# LCD_shield_C144MVGD_v1.net
KiCad netlist of a schematic drawn in EAGLE
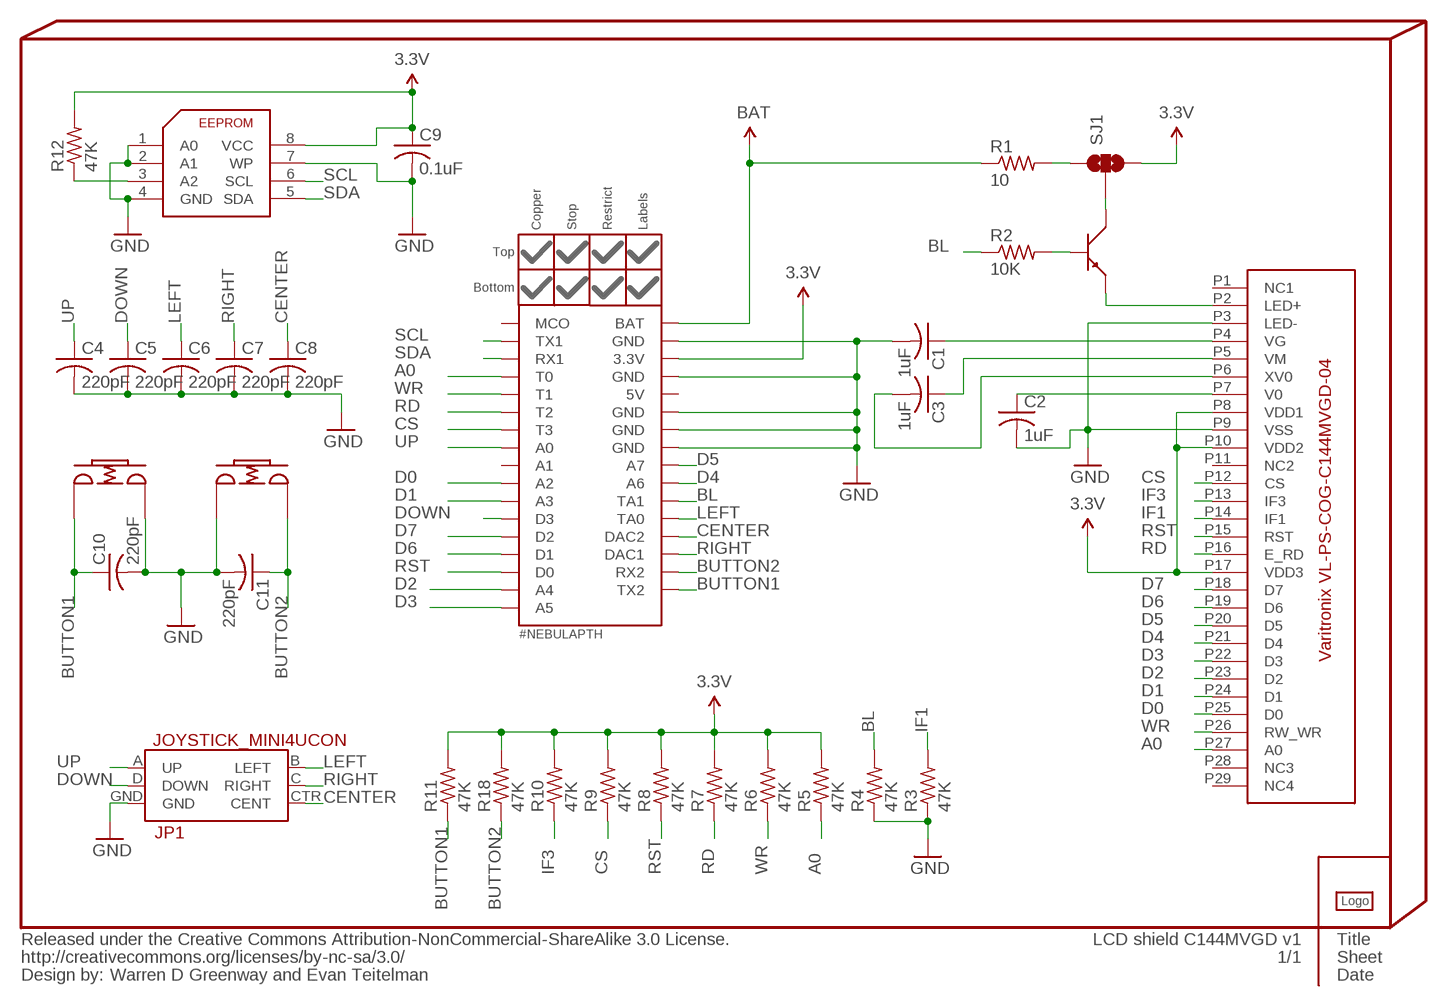
[diagram p0: schematic, sheet 1]

(export (version "E")
  (design (tool "Eeschema 10.0.6"))
  (components
    (comp (ref "C1")
      (value "1uF")
      (footprint "eagle-import:C0402")
      (libsource (lib "eagle-import") (part "C-USC0402"))
    )
    (comp (ref "C2")
      (value "1uF")
      (footprint "eagle-import:C0402")
      (libsource (lib "eagle-import") (part "C-USC0402"))
    )
    (comp (ref "C3")
      (value "1uF")
      (footprint "eagle-import:C0402")
      (libsource (lib "eagle-import") (part "C-USC0402"))
    )
    (comp (ref "C4")
      (value "220pF")
      (footprint "eagle-import:C0402")
      (libsource (lib "eagle-import") (part "C-USC0402"))
    )
    (comp (ref "C5")
      (value "220pF")
      (footprint "eagle-import:C0402")
      (libsource (lib "eagle-import") (part "C-USC0402"))
    )
    (comp (ref "C6")
      (value "220pF")
      (footprint "eagle-import:C0402")
      (libsource (lib "eagle-import") (part "C-USC0402"))
    )
    (comp (ref "C7")
      (value "220pF")
      (footprint "eagle-import:C0402")
      (libsource (lib "eagle-import") (part "C-USC0402"))
    )
    (comp (ref "C8")
      (value "220pF")
      (footprint "eagle-import:C0402")
      (libsource (lib "eagle-import") (part "C-USC0402"))
    )
    (comp (ref "C9")
      (value "0.1uF")
      (footprint "eagle-import:C0402")
      (libsource (lib "eagle-import") (part "C-USC0402"))
    )
    (comp (ref "C10")
      (value "220pF")
      (footprint "eagle-import:C0402")
      (libsource (lib "eagle-import") (part "C-USC0402"))
    )
    (comp (ref "C11")
      (value "220pF")
      (footprint "eagle-import:C0402")
      (libsource (lib "eagle-import") (part "C-USC0402"))
    )
    (comp (ref "INFO3")
      (value "Warren D Greenway and Evan Teitelman")
      (footprint "eagle-import:%CC-NC-SA")
      (libsource (lib "eagle-import") (part "%CC-NC-SA"))
    )
    (comp (ref "JP1")
      (value "JOYSTICK_MINI4UCON")
      (footprint "eagle-import:JOYSTICK_MINI")
      (libsource (lib "eagle-import") (part "JOYSTICK_MINI4UCON"))
    )
    (comp (ref "LOGO1")
      (value "#PYGMYLOGOLARGE")
      (footprint "eagle-import:#PYGMYLOGO")
      (libsource (lib "eagle-import") (part "#PYGMYLOGOLARGE"))
    )
    (comp (ref "NEBULA1")
      (value "#NEBULAPTH")
      (footprint "eagle-import:#NEBULA-PTH")
      (libsource (lib "eagle-import") (part "#NEBULAPTH"))
    )
    (comp (ref "R1")
      (value "10")
      (footprint "eagle-import:R0805")
      (libsource (lib "eagle-import") (part "R-US_R0805"))
    )
    (comp (ref "R2")
      (value "10K")
      (footprint "eagle-import:R0402")
      (libsource (lib "eagle-import") (part "R-US_R0402"))
    )
    (comp (ref "R3")
      (value "47K")
      (footprint "eagle-import:R0402")
      (libsource (lib "eagle-import") (part "R-US_R0402"))
    )
    (comp (ref "R4")
      (value "47K")
      (footprint "eagle-import:R0402")
      (libsource (lib "eagle-import") (part "R-US_R0402"))
    )
    (comp (ref "R5")
      (value "47K")
      (footprint "eagle-import:R0402")
      (libsource (lib "eagle-import") (part "R-US_R0402"))
    )
    (comp (ref "R6")
      (value "47K")
      (footprint "eagle-import:R0402")
      (libsource (lib "eagle-import") (part "R-US_R0402"))
    )
    (comp (ref "R7")
      (value "47K")
      (footprint "eagle-import:R0402")
      (libsource (lib "eagle-import") (part "R-US_R0402"))
    )
    (comp (ref "R8")
      (value "47K")
      (footprint "eagle-import:R0402")
      (libsource (lib "eagle-import") (part "R-US_R0402"))
    )
    (comp (ref "R9")
      (value "47K")
      (footprint "eagle-import:R0402")
      (libsource (lib "eagle-import") (part "R-US_R0402"))
    )
    (comp (ref "R10")
      (value "47K")
      (footprint "eagle-import:R0402")
      (libsource (lib "eagle-import") (part "R-US_R0402"))
    )
    (comp (ref "R11")
      (value "47K")
      (footprint "eagle-import:R0402")
      (libsource (lib "eagle-import") (part "R-US_R0402"))
    )
    (comp (ref "R12")
      (value "47K")
      (footprint "eagle-import:R0402")
      (libsource (lib "eagle-import") (part "R-US_R0402"))
    )
    (comp (ref "R18")
      (value "47K")
      (footprint "eagle-import:R0402")
      (libsource (lib "eagle-import") (part "R-US_R0402"))
    )
    (comp (ref "SJ1")
      (value "SOLDERJUMPER_2WAYPASTE1&2")
      (footprint "eagle-import:SJ_3_PASTE1&2")
      (libsource (lib "eagle-import") (part "SOLDERJUMPER_2WAYPASTE1&2"))
    )
    (comp (ref "U1")
      (value "VARITRONIX_VL-PS-COG-C144MVGD-04FOLDED")
      (footprint "eagle-import:VARITRONIX_C144MVGD_FOLDED")
      (libsource (lib "eagle-import") (part "VARITRONIX_VL-PS-COG-C144MVGD-04FOLDED"))
    )
    (comp (ref "U2")
      (value "BIPOLAR-PMBT6428")
      (footprint "eagle-import:DUBLIB_SOT23")
      (libsource (lib "eagle-import") (part "BIPOLAR-PMBT6428"))
    )
    (comp (ref "U3")
      (value "EEPROM-ATMEL-AT24HC02B")
      (footprint "eagle-import:TSSOP8")
      (libsource (lib "eagle-import") (part "EEPROM-ATMEL-AT24HC02B"))
    )
    (comp (ref "U4")
      (value "SWITCH-ALPS-SKRG")
      (footprint "eagle-import:SWITCH-2P-5MM")
      (libsource (lib "eagle-import") (part "SWITCH-ALPS-SKRG"))
    )
    (comp (ref "U5")
      (value "SWITCH-ALPS-SKRG")
      (footprint "eagle-import:SWITCH-2P-5MM")
      (libsource (lib "eagle-import") (part "SWITCH-ALPS-SKRG"))
    )
  )
  (nets
    (net (code "1") (name "/A0") (class "Default")
      (node (ref "NEBULA1") (pin "T0") (pinfunction "T0_T0") (pintype "bidirectional"))
      (node (ref "R5") (pin "1") (pinfunction "1_1") (pintype "passive"))
      (node (ref "U1") (pin "P27") (pinfunction "A0_P27") (pintype "bidirectional"))
    )
    (net (code "2") (name "/BL") (class "Default")
      (node (ref "NEBULA1") (pin "TA1") (pinfunction "TA1_TA1") (pintype "bidirectional"))
      (node (ref "R2") (pin "1") (pinfunction "1_1") (pintype "passive"))
      (node (ref "R4") (pin "2") (pinfunction "2_2") (pintype "passive"))
    )
    (net (code "3") (name "/BUTTON1") (class "Default")
      (node (ref "C10") (pin "1") (pinfunction "1_1") (pintype "passive"))
      (node (ref "NEBULA1") (pin "COM2_TX") (pinfunction "TX2_COM2_TX") (pintype "bidirectional"))
      (node (ref "R11") (pin "1") (pinfunction "1_1") (pintype "passive"))
      (node (ref "U4") (pin "P1") (pinfunction "P1_P1") (pintype "bidirectional"))
    )
    (net (code "4") (name "/BUTTON2") (class "Default")
      (node (ref "C11") (pin "1") (pinfunction "1_1") (pintype "passive"))
      (node (ref "NEBULA1") (pin "COM2_RX") (pinfunction "RX2_COM2_RX") (pintype "bidirectional"))
      (node (ref "R18") (pin "1") (pinfunction "1_1") (pintype "passive"))
      (node (ref "U5") (pin "P2") (pinfunction "P2_P2") (pintype "bidirectional"))
    )
    (net (code "5") (name "/CENTER") (class "Default")
      (node (ref "C8") (pin "1") (pinfunction "1_1") (pintype "passive"))
      (node (ref "JP1") (pin "CTR") (pinfunction "CENT_CTR") (pintype "bidirectional"))
      (node (ref "NEBULA1") (pin "DAC2") (pinfunction "DAC2_DAC2") (pintype "bidirectional"))
    )
    (net (code "6") (name "/CS") (class "Default")
      (node (ref "NEBULA1") (pin "T3") (pinfunction "T3_T3") (pintype "bidirectional"))
      (node (ref "R9") (pin "1") (pinfunction "1_1") (pintype "passive"))
      (node (ref "U1") (pin "P12") (pinfunction "CS_P12") (pintype "bidirectional"))
    )
    (net (code "7") (name "/D0") (class "Default")
      (node (ref "NEBULA1") (pin "A2") (pinfunction "A2_A2") (pintype "bidirectional"))
      (node (ref "U1") (pin "P25") (pinfunction "D0_P25") (pintype "bidirectional"))
    )
    (net (code "8") (name "/D1") (class "Default")
      (node (ref "NEBULA1") (pin "A3") (pinfunction "A3_A3") (pintype "bidirectional"))
      (node (ref "U1") (pin "P24") (pinfunction "D1_P24") (pintype "bidirectional"))
    )
    (net (code "9") (name "/D2") (class "Default")
      (node (ref "NEBULA1") (pin "A4") (pinfunction "A4_A4") (pintype "bidirectional"))
      (node (ref "U1") (pin "P23") (pinfunction "D2_P23") (pintype "bidirectional"))
    )
    (net (code "10") (name "/D3") (class "Default")
      (node (ref "NEBULA1") (pin "A5") (pinfunction "A5_A5") (pintype "bidirectional"))
      (node (ref "U1") (pin "P22") (pinfunction "D3_P22") (pintype "bidirectional"))
    )
    (net (code "11") (name "/D4") (class "Default")
      (node (ref "NEBULA1") (pin "A6") (pinfunction "A6_A6") (pintype "bidirectional"))
      (node (ref "U1") (pin "P21") (pinfunction "D4_P21") (pintype "bidirectional"))
    )
    (net (code "12") (name "/D5") (class "Default")
      (node (ref "NEBULA1") (pin "A7") (pinfunction "A7_A7") (pintype "bidirectional"))
      (node (ref "U1") (pin "P20") (pinfunction "D5_P20") (pintype "bidirectional"))
    )
    (net (code "13") (name "/D6") (class "Default")
      (node (ref "NEBULA1") (pin "D1") (pinfunction "D1_D1") (pintype "bidirectional"))
      (node (ref "U1") (pin "P19") (pinfunction "D6_P19") (pintype "bidirectional"))
    )
    (net (code "14") (name "/D7") (class "Default")
      (node (ref "NEBULA1") (pin "D2") (pinfunction "D2_D2") (pintype "bidirectional"))
      (node (ref "U1") (pin "P18") (pinfunction "D7_P18") (pintype "bidirectional"))
    )
    (net (code "15") (name "/DOWN") (class "Default")
      (node (ref "C5") (pin "1") (pinfunction "1_1") (pintype "passive"))
      (node (ref "JP1") (pin "D") (pinfunction "DOWN_D") (pintype "bidirectional"))
      (node (ref "NEBULA1") (pin "D3") (pinfunction "D3_D3") (pintype "bidirectional"))
    )
    (net (code "16") (name "/IF1") (class "Default")
      (node (ref "R3") (pin "2") (pinfunction "2_2") (pintype "passive"))
      (node (ref "U1") (pin "P14") (pinfunction "IF1_P14") (pintype "bidirectional"))
    )
    (net (code "17") (name "/IF3") (class "Default")
      (node (ref "R10") (pin "1") (pinfunction "1_1") (pintype "passive"))
      (node (ref "U1") (pin "P13") (pinfunction "IF3_P13") (pintype "bidirectional"))
    )
    (net (code "18") (name "/LEFT") (class "Default")
      (node (ref "C6") (pin "1") (pinfunction "1_1") (pintype "passive"))
      (node (ref "JP1") (pin "B") (pinfunction "LEFT_B") (pintype "bidirectional"))
      (node (ref "NEBULA1") (pin "TA0") (pinfunction "TA0_TA0") (pintype "bidirectional"))
    )
    (net (code "19") (name "/RD") (class "Default")
      (node (ref "NEBULA1") (pin "T2") (pinfunction "T2_T2") (pintype "bidirectional"))
      (node (ref "R7") (pin "1") (pinfunction "1_1") (pintype "passive"))
      (node (ref "U1") (pin "P16") (pinfunction "E_RD_P16") (pintype "bidirectional"))
    )
    (net (code "20") (name "/RIGHT") (class "Default")
      (node (ref "C7") (pin "1") (pinfunction "1_1") (pintype "passive"))
      (node (ref "JP1") (pin "C") (pinfunction "RIGHT_C") (pintype "bidirectional"))
      (node (ref "NEBULA1") (pin "DAC1") (pinfunction "DAC1_DAC1") (pintype "bidirectional"))
    )
    (net (code "21") (name "/RST") (class "Default")
      (node (ref "NEBULA1") (pin "D0") (pinfunction "D0_D0") (pintype "bidirectional"))
      (node (ref "R8") (pin "1") (pinfunction "1_1") (pintype "passive"))
      (node (ref "U1") (pin "P15") (pinfunction "RST_P15") (pintype "bidirectional"))
    )
    (net (code "22") (name "/SCL") (class "Default")
      (node (ref "NEBULA1") (pin "COM1_TX") (pinfunction "TX1_COM1_TX") (pintype "bidirectional"))
      (node (ref "U3") (pin "6") (pinfunction "SCL_6") (pintype "bidirectional"))
    )
    (net (code "23") (name "/SDA") (class "Default")
      (node (ref "NEBULA1") (pin "COM1_RX") (pinfunction "RX1_COM1_RX") (pintype "bidirectional"))
      (node (ref "U3") (pin "5") (pinfunction "SDA_5") (pintype "bidirectional"))
    )
    (net (code "24") (name "/UP") (class "Default")
      (node (ref "C4") (pin "1") (pinfunction "1_1") (pintype "passive"))
      (node (ref "JP1") (pin "A") (pinfunction "UP_A") (pintype "bidirectional"))
      (node (ref "NEBULA1") (pin "A0") (pinfunction "A0_A0") (pintype "bidirectional"))
    )
    (net (code "25") (name "/WR") (class "Default")
      (node (ref "NEBULA1") (pin "T1") (pinfunction "T1_T1") (pintype "bidirectional"))
      (node (ref "R6") (pin "1") (pinfunction "1_1") (pintype "passive"))
      (node (ref "U1") (pin "P26") (pinfunction "RW_WR_P26") (pintype "bidirectional"))
    )
    (net (code "26") (name "@3.3V") (class "Default")
      (node (ref "C9") (pin "1") (pinfunction "1_1") (pintype "passive"))
      (node (ref "NEBULA1") (pin "3.3V") (pinfunction "3.3V_3.3V") (pintype "bidirectional"))
      (node (ref "R10") (pin "2") (pinfunction "2_2") (pintype "passive"))
      (node (ref "R11") (pin "2") (pinfunction "2_2") (pintype "passive"))
      (node (ref "R12") (pin "2") (pinfunction "2_2") (pintype "passive"))
      (node (ref "R18") (pin "2") (pinfunction "2_2") (pintype "passive"))
      (node (ref "R5") (pin "2") (pinfunction "2_2") (pintype "passive"))
      (node (ref "R6") (pin "2") (pinfunction "2_2") (pintype "passive"))
      (node (ref "R7") (pin "2") (pinfunction "2_2") (pintype "passive"))
      (node (ref "R8") (pin "2") (pinfunction "2_2") (pintype "passive"))
      (node (ref "R9") (pin "2") (pinfunction "2_2") (pintype "passive"))
      (node (ref "SJ1") (pin "3") (pinfunction "3_3") (pintype "passive"))
      (node (ref "U1") (pin "P10") (pinfunction "VDD2_P10") (pintype "bidirectional"))
      (node (ref "U1") (pin "P17") (pinfunction "VDD3_P17") (pintype "bidirectional"))
      (node (ref "U1") (pin "P8") (pinfunction "VDD1_P8") (pintype "bidirectional"))
      (node (ref "U3") (pin "8") (pinfunction "VCC_8") (pintype "bidirectional"))
    )
    (net (code "27") (name "@BAT") (class "Default")
      (node (ref "NEBULA1") (pin "BAT") (pinfunction "BAT_BAT") (pintype "bidirectional"))
      (node (ref "R1") (pin "1") (pinfunction "1_1") (pintype "passive"))
    )
    (net (code "28") (name "@GND") (class "Default")
      (node (ref "C1") (pin "2") (pinfunction "2_2") (pintype "passive"))
      (node (ref "C10") (pin "2") (pinfunction "2_2") (pintype "passive"))
      (node (ref "C11") (pin "2") (pinfunction "2_2") (pintype "passive"))
      (node (ref "C2") (pin "2") (pinfunction "2_2") (pintype "passive"))
      (node (ref "C4") (pin "2") (pinfunction "2_2") (pintype "passive"))
      (node (ref "C5") (pin "2") (pinfunction "2_2") (pintype "passive"))
      (node (ref "C6") (pin "2") (pinfunction "2_2") (pintype "passive"))
      (node (ref "C7") (pin "2") (pinfunction "2_2") (pintype "passive"))
      (node (ref "C8") (pin "2") (pinfunction "2_2") (pintype "passive"))
      (node (ref "C9") (pin "2") (pinfunction "2_2") (pintype "passive"))
      (node (ref "JP1") (pin "GND") (pinfunction "GND_GND") (pintype "bidirectional"))
      (node (ref "NEBULA1") (pin "GND1") (pinfunction "GND_GND1") (pintype "bidirectional"))
      (node (ref "NEBULA1") (pin "GND2") (pinfunction "GND_GND2") (pintype "bidirectional"))
      (node (ref "NEBULA1") (pin "GND3") (pinfunction "GND_GND3") (pintype "bidirectional"))
      (node (ref "NEBULA1") (pin "GND4") (pinfunction "GND_GND4") (pintype "bidirectional"))
      (node (ref "NEBULA1") (pin "GND5") (pinfunction "GND_GND5") (pintype "bidirectional"))
      (node (ref "R3") (pin "1") (pinfunction "1_1") (pintype "passive"))
      (node (ref "R4") (pin "1") (pinfunction "1_1") (pintype "passive"))
      (node (ref "U1") (pin "P3") (pinfunction "LED-_P3") (pintype "bidirectional"))
      (node (ref "U1") (pin "P9") (pinfunction "VSS_P9") (pintype "bidirectional"))
      (node (ref "U3") (pin "1") (pinfunction "A0_1") (pintype "bidirectional"))
      (node (ref "U3") (pin "2") (pinfunction "A1_2") (pintype "bidirectional"))
      (node (ref "U3") (pin "4") (pinfunction "GND_4") (pintype "bidirectional"))
      (node (ref "U3") (pin "7") (pinfunction "WP_7") (pintype "bidirectional"))
      (node (ref "U4") (pin "P2") (pinfunction "P2_P2") (pintype "bidirectional"))
      (node (ref "U5") (pin "P1") (pinfunction "P1_P1") (pintype "bidirectional"))
    )
    (net (code "29") (name "Net-(R1-Pad2)") (class "Default")
      (node (ref "R1") (pin "2") (pinfunction "2_2") (pintype "passive"))
      (node (ref "SJ1") (pin "1") (pinfunction "1_1") (pintype "passive"))
    )
    (net (code "30") (name "Net-(R2-Pad2)") (class "Default")
      (node (ref "R2") (pin "2") (pinfunction "2_2") (pintype "passive"))
      (node (ref "U2") (pin "1") (pinfunction "1_1") (pintype "bidirectional"))
    )
    (net (code "31") (name "Net-(SJ1-Pad2)") (class "Default")
      (node (ref "SJ1") (pin "2") (pinfunction "2_2") (pintype "passive"))
      (node (ref "U2") (pin "3") (pinfunction "3_3") (pintype "bidirectional"))
    )
    (net (code "32") (name "Net-(U1-LED+)") (class "Default")
      (node (ref "U1") (pin "P2") (pinfunction "LED+_P2") (pintype "bidirectional"))
      (node (ref "U2") (pin "2") (pinfunction "2_2") (pintype "bidirectional"))
    )
    (net (code "33") (name "Net-(U1-V0)") (class "Default")
      (node (ref "C2") (pin "1") (pinfunction "1_1") (pintype "passive"))
      (node (ref "U1") (pin "P7") (pinfunction "V0_P7") (pintype "bidirectional"))
    )
    (net (code "34") (name "Net-(U1-VG)") (class "Default")
      (node (ref "C1") (pin "1") (pinfunction "1_1") (pintype "passive"))
      (node (ref "U1") (pin "P4") (pinfunction "VG_P4") (pintype "bidirectional"))
    )
    (net (code "35") (name "Net-(U1-VM)") (class "Default")
      (node (ref "C3") (pin "1") (pinfunction "1_1") (pintype "passive"))
      (node (ref "U1") (pin "P5") (pinfunction "VM_P5") (pintype "bidirectional"))
    )
    (net (code "36") (name "Net-(U1-XV0)") (class "Default")
      (node (ref "C3") (pin "2") (pinfunction "2_2") (pintype "passive"))
      (node (ref "U1") (pin "P6") (pinfunction "XV0_P6") (pintype "bidirectional"))
    )
    (net (code "37") (name "Net-(U3-A2)") (class "Default")
      (node (ref "R12") (pin "1") (pinfunction "1_1") (pintype "passive"))
      (node (ref "U3") (pin "3") (pinfunction "A2_3") (pintype "bidirectional"))
    )
    (net (code "38") (name "unconnected-(NEBULA1-Pad5V)") (class "Default")
      (node (ref "NEBULA1") (pin "5V") (pinfunction "5V_5V") (pintype "bidirectional"))
    )
    (net (code "39") (name "unconnected-(NEBULA1-PadA1)") (class "Default")
      (node (ref "NEBULA1") (pin "A1") (pinfunction "A1_A1") (pintype "bidirectional"))
    )
    (net (code "40") (name "unconnected-(NEBULA1-PadMCO)") (class "Default")
      (node (ref "NEBULA1") (pin "MCO") (pinfunction "MCO_MCO") (pintype "bidirectional"))
    )
    (net (code "41") (name "unconnected-(U1-NC1-PadP1)") (class "Default")
      (node (ref "U1") (pin "P1") (pinfunction "NC1_P1") (pintype "bidirectional"))
    )
    (net (code "42") (name "unconnected-(U1-NC2-PadP11)") (class "Default")
      (node (ref "U1") (pin "P11") (pinfunction "NC2_P11") (pintype "bidirectional"))
    )
    (net (code "43") (name "unconnected-(U1-NC3-PadP28)") (class "Default")
      (node (ref "U1") (pin "P28") (pinfunction "NC3_P28") (pintype "bidirectional"))
    )
    (net (code "44") (name "unconnected-(U1-NC4-PadP29)") (class "Default")
      (node (ref "U1") (pin "P29") (pinfunction "NC4_P29") (pintype "bidirectional"))
    )
  )
)
